# MCont_V1_0.net
KiCad netlist of a schematic drawn in Altium Designer
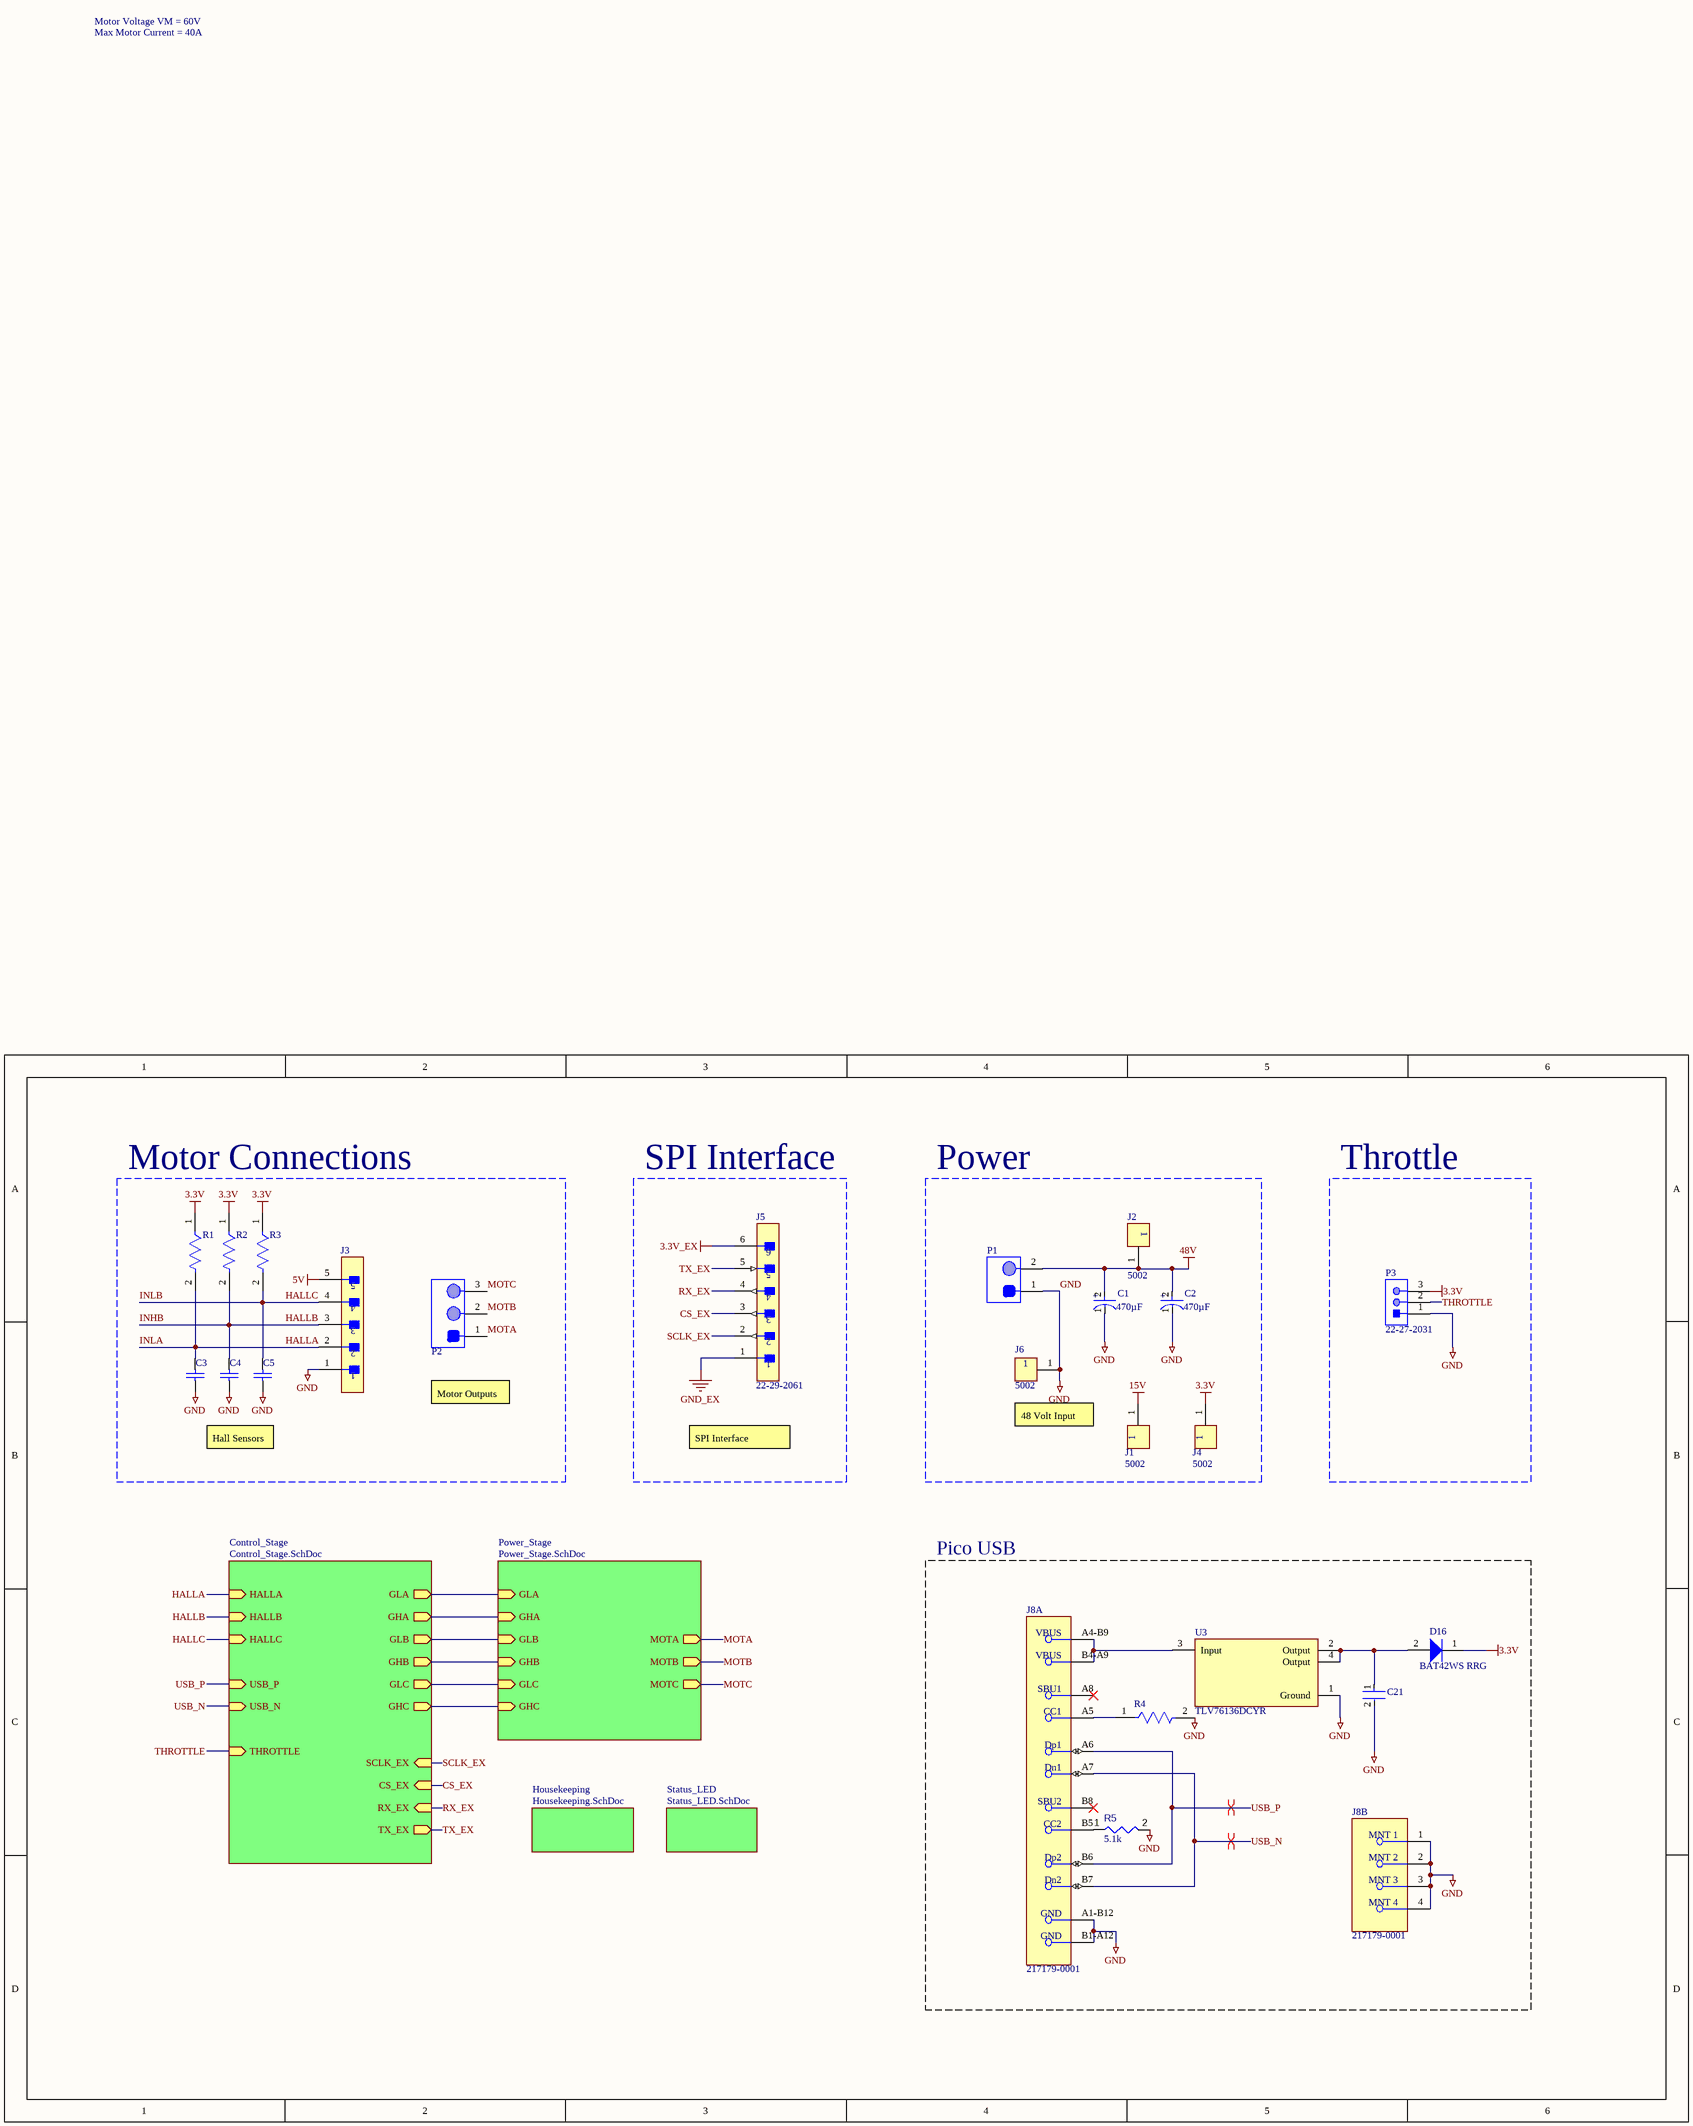
[diagram p0: MCont_V1.0.SchDoc]

(export (version "E")
  (design (tool "Eeschema 10.0.6"))
  (components
    (comp (ref "C1")
      (value "ESH477M100AM2AA")
      (footprint "FP-ESH477M100AM2AA-MFG")
      (description "ESH477M100AM2AA Radial Can ALUMINUM ELECTROLYTIC CAPACITOR ESH 100V 470muF ±20% 0.630Dia 16.00mm")
      (fields (field (name "TOLERANCE") "20%") (field (name "CAPACITANCE") "470µF"))
      (libsource (lib "Altium Content Vault") (part "cf48714ba7e38822c1575c7ec0b6d1f"))
    )
    (comp (ref "C2")
      (value "ESH477M100AM2AA")
      (footprint "FP-ESH477M100AM2AA-MFG")
      (description "ESH477M100AM2AA Radial Can ALUMINUM ELECTROLYTIC CAPACITOR ESH 100V 470muF ±20% 0.630Dia 16.00mm")
      (fields (field (name "TOLERANCE") "20%") (field (name "CAPACITANCE") "470µF"))
      (libsource (lib "Altium Content Vault") (part "cf48714ba7e38822c1575c7ec0b6d1f"))
    )
    (comp (ref "C3")
      (value "VJ0603Y102KXACW1BC")
      (footprint "CAPC1608X95X40NL15T15")
      (fields (field (name "MANUFACTURER") "Vitramon"))
      (libsource (lib "Altium Content Vault") (part "CAP"))
    )
    (comp (ref "C4")
      (value "VJ0603Y102KXACW1BC")
      (footprint "CAPC1608X95X40NL15T15")
      (fields (field (name "MANUFACTURER") "Vitramon"))
      (libsource (lib "Altium Content Vault") (part "CAP"))
    )
    (comp (ref "C5")
      (value "VJ0603Y102KXACW1BC")
      (footprint "CAPC1608X95X40NL15T15")
      (fields (field (name "MANUFACTURER") "Vitramon"))
      (libsource (lib "Altium Content Vault") (part "CAP"))
    )
    (comp (ref "C21")
      (value "CC0603KRX5R6BB106")
      (footprint "FP-CC0603-DC-MFG")
      (description "CAP CER 10UF 10V X5R 0603")
      (fields (field (name "TOLERANCE") "10%"))
      (libsource (lib "Altium Content Vault") (part "b4654b650e69147ec39a6b967a45e02"))
    )
    (comp (ref "D16")
      (value "BAT42WS RRG")
      (footprint "BAT42WS RRG-Footprint-1")
      (description "Schottky Diode, 30V, 0.2A, Sod-323F Rohs Compliant: Yes")
      (libsource (lib "CEV Electrical New") (part "BAT42WS RRG-Symbol-1"))
    )
    (comp (ref "J1")
      (value "5002")
      (footprint "FP-5002-MFG")
      (description "PC TEST POINT MINIATURE WHITE")
      (libsource (lib "") (part "1e4615820a309e3ce90f9e6d957b7fa_1"))
    )
    (comp (ref "J2")
      (value "5002")
      (footprint "FP-5002-MFG")
      (description "PC TEST POINT MINIATURE WHITE")
      (libsource (lib "") (part "1e4615820a309e3ce90f9e6d957b7fa_2"))
    )
    (comp (ref "J3")
      (value "22-29-2051")
      (footprint "FP-22-29-2051-MFG")
      (description "2.54MM KK HDR VT FRICLK VRA .5AU")
      (libsource (lib "Altium Content Vault") (part "bf93c07fd2649a848d0ec8585582aab"))
    )
    (comp (ref "J4")
      (value "5002")
      (footprint "FP-5002-MFG")
      (description "PC TEST POINT MINIATURE WHITE")
      (libsource (lib "") (part "1e4615820a309e3ce90f9e6d957b7fa_1"))
    )
    (comp (ref "J5")
      (value "22-29-2061")
      (footprint "FP-22-29-2061-MFG")
      (description "CONN HEADER VERT 6POS 2.54MM")
      (libsource (lib "Altium Content Vault") (part "f2cb566baf1c37ab5a3b8e90bbeafd6"))
    )
    (comp (ref "J6")
      (value "5002")
      (footprint "FP-5002-MFG")
      (description "PC TEST POINT MINIATURE WHITE")
      (libsource (lib "Altium Content Vault") (part "1e4615820a309e3ce90f9e6d957b7fa"))
    )
    (comp (ref "J8")
      (value "217179-0001")
      (footprint "FP-2171790001-MFG")
      (description "CONN RCP USB2.0 TYP C 24P SMD RA")
      (libsource (lib "Altium Content Vault") (part "8b86497a633d14b3f74642136fc0ce6"))
    )
    (comp (ref "P1")
      (value "VP0265540000G")
      (footprint "VP0265540000G-Footprint-1")
      (description "VP10.16-2P slot screws Cr3+ zinc, solder foot bright tin, steel stamping clamp")
      (libsource (lib "CEV Electrical") (part "VP0265540000G-Symbol-1"))
    )
    (comp (ref "P2")
      (value "VP0365540000G")
      (footprint "VP0365540000G-Footprint-1")
      (description "VP10.16-3P slot screws Cr3 zinc, solder foot bright tin, steel stamping clamp")
      (libsource (lib "CEV Electrical") (part "VP0365540000G-Symbol-1"))
    )
    (comp (ref "P3")
      (value "22-27-2031")
      (footprint "MOLX-22-27-2031_V")
      (fields (field (name "MANUFACTURER") "Molex"))
      (libsource (lib "Altium Content Vault") (part "CN-1P-M-R3"))
    )
    (comp (ref "R1")
      (value "RC0603FR-0710KL")
      (footprint "FP-RC0603-0_55-IPC_C")
      (description "RES 10K OHM 1% 1/10W 0603")
      (fields (field (name "TOLERANCE") "1%"))
      (libsource (lib "Altium Content Vault") (part "1029c3af85768c4190bb7ad29bc67b5"))
    )
    (comp (ref "R2")
      (value "RC0603FR-0710KL")
      (footprint "FP-RC0603-0_55-IPC_C")
      (description "RES 10K OHM 1% 1/10W 0603")
      (fields (field (name "TOLERANCE") "1%"))
      (libsource (lib "Altium Content Vault") (part "1029c3af85768c4190bb7ad29bc67b5"))
    )
    (comp (ref "R3")
      (value "RC0603FR-0710KL")
      (footprint "FP-RC0603-0_55-IPC_C")
      (description "RES 10K OHM 1% 1/10W 0603")
      (fields (field (name "TOLERANCE") "1%"))
      (libsource (lib "Altium Content Vault") (part "1029c3af85768c4190bb7ad29bc67b5"))
    )
    (comp (ref "R4")
      (value "ERJ-3EKF5101V")
      (footprint "FP-ERJ3EK-MFG")
      (description "RES SMD 5.1K OHM 1% 1/10W 0603")
      (fields (field (name "TOLERANCE") "1%"))
      (libsource (lib "Altium Content Vault") (part "1029c3af85768c4190bb7ad29bc67b5"))
    )
    (comp (ref "R5")
      (value "5.1k")
      (footprint "FP-ERJ3EK-IPC_A")
      (fields
        (field (name "TOLERANCE") "1%")
        (field (name "POWER") "100mW")
        (field (name "Comment") "ERJ-3EKF5101V")
      )
      (libsource (lib "CEV Electrical") (part "RES-2"))
    )
    (comp (ref "U3")
      (value "TLV76136DCYR")
      (footprint "TLV76136DCYR-Footprint-1")
      (description "1A 16V high-PSRR linear voltage regulator 4-SOT-223 -40 to 125")
      (libsource (lib "CEV Electrical New") (part "TLV76136DCYR-Symbol-1"))
    )
  )
  (nets
    (net (code "1") (name "/CS_EX") (class "Default")
      (node (ref "J5") (pin "3") (pinfunction "3_3") (pintype "output"))
    )
    (net (code "8") (name "/HALLA") (class "Default")
      (node (ref "C3") (pin "2") (pinfunction "2_2") (pintype "passive"))
      (node (ref "J3") (pin "2") (pinfunction "2_2") (pintype "passive"))
      (node (ref "R1") (pin "2") (pinfunction "2_2") (pintype "passive"))
    )
    (net (code "9") (name "/HALLB") (class "Default")
      (node (ref "C4") (pin "2") (pinfunction "2_2") (pintype "passive"))
      (node (ref "J3") (pin "3") (pinfunction "3_3") (pintype "passive"))
      (node (ref "R2") (pin "2") (pinfunction "2_2") (pintype "passive"))
    )
    (net (code "10") (name "/HALLC") (class "Default")
      (node (ref "C5") (pin "2") (pinfunction "2_2") (pintype "passive"))
      (node (ref "J3") (pin "4") (pinfunction "4_4") (pintype "passive"))
      (node (ref "R3") (pin "2") (pinfunction "2_2") (pintype "passive"))
    )
    (net (code "11") (name "/MOTA") (class "Default")
      (node (ref "P2") (pin "1") (pinfunction "1_1") (pintype "passive"))
    )
    (net (code "12") (name "/MOTB") (class "Default")
      (node (ref "P2") (pin "2") (pinfunction "2_2") (pintype "passive"))
    )
    (net (code "13") (name "/MOTC") (class "Default")
      (node (ref "P2") (pin "3") (pinfunction "3_3") (pintype "passive"))
    )
    (net (code "14") (name "/RX_EX") (class "Default")
      (node (ref "J5") (pin "4") (pinfunction "4_4") (pintype "output"))
    )
    (net (code "15") (name "/SCLK_EX") (class "Default")
      (node (ref "J5") (pin "2") (pinfunction "2_2") (pintype "output"))
    )
    (net (code "16") (name "/THROTTLE") (class "Default")
      (node (ref "P3") (pin "2") (pinfunction "2_2") (pintype "passive"))
    )
    (net (code "17") (name "/TX_EX") (class "Default")
      (node (ref "J5") (pin "5") (pinfunction "5_5") (pintype "input"))
    )
    (net (code "18") (name "/USB_N") (class "Default")
      (node (ref "J8") (pin "A7") (pinfunction "Dn1_A7") (pintype "bidirectional"))
      (node (ref "J8") (pin "B7") (pinfunction "Dn2_B7") (pintype "bidirectional"))
    )
    (net (code "19") (name "/USB_P") (class "Default")
      (node (ref "J8") (pin "A6") (pinfunction "Dp1_A6") (pintype "bidirectional"))
      (node (ref "J8") (pin "B6") (pinfunction "Dp2_B6") (pintype "bidirectional"))
    )
    (net (code "20") (name "3.3V") (class "Default")
      (node (ref "D16") (pin "1") (pinfunction "K_1") (pintype "passive"))
      (node (ref "J4") (pin "1") (pinfunction "1_1") (pintype "passive"))
      (node (ref "P3") (pin "3") (pinfunction "3_3") (pintype "passive"))
      (node (ref "R1") (pin "1") (pinfunction "1_1") (pintype "passive"))
      (node (ref "R2") (pin "1") (pinfunction "1_1") (pintype "passive"))
      (node (ref "R3") (pin "1") (pinfunction "1_1") (pintype "passive"))
    )
    (net (code "21") (name "3.3V_EX") (class "Default")
      (node (ref "J5") (pin "6") (pinfunction "6_6") (pintype "power_in"))
    )
    (net (code "22") (name "5V") (class "Default")
      (node (ref "J3") (pin "5") (pinfunction "5_5") (pintype "passive"))
    )
    (net (code "23") (name "15V") (class "Default")
      (node (ref "J1") (pin "1") (pinfunction "1_1") (pintype "passive"))
    )
    (net (code "24") (name "48V") (class "Default")
      (node (ref "C1") (pin "2") (pinfunction "A_2") (pintype "passive"))
      (node (ref "C2") (pin "2") (pinfunction "A_2") (pintype "passive"))
      (node (ref "J2") (pin "1") (pinfunction "1_1") (pintype "passive"))
      (node (ref "P1") (pin "2") (pinfunction "2_2") (pintype "passive"))
    )
    (net (code "25") (name "GND") (class "Default")
      (node (ref "C1") (pin "1") (pinfunction "C_1") (pintype "passive"))
      (node (ref "C2") (pin "1") (pinfunction "C_1") (pintype "passive"))
      (node (ref "C21") (pin "2") (pinfunction "2_2") (pintype "passive"))
      (node (ref "C3") (pin "1") (pinfunction "1_1") (pintype "passive"))
      (node (ref "C4") (pin "1") (pinfunction "1_1") (pintype "passive"))
      (node (ref "C5") (pin "1") (pinfunction "1_1") (pintype "passive"))
      (node (ref "J3") (pin "1") (pinfunction "1_1") (pintype "passive"))
      (node (ref "J6") (pin "1") (pinfunction "1_1") (pintype "passive"))
      (node (ref "J8") (pin "1") (pinfunction "MNT_1_1") (pintype "passive"))
      (node (ref "J8") (pin "2") (pinfunction "MNT_2_2") (pintype "passive"))
      (node (ref "J8") (pin "3") (pinfunction "MNT_3_3") (pintype "power_in"))
      (node (ref "J8") (pin "4") (pinfunction "MNT_4_4") (pintype "power_in"))
      (node (ref "J8") (pin "A1-B12") (pinfunction "GND_A1-B12") (pintype "power_in"))
      (node (ref "J8") (pin "B1-A12") (pinfunction "GND_B1-A12") (pintype "power_in"))
      (node (ref "P1") (pin "1") (pinfunction "1_1") (pintype "passive"))
      (node (ref "P3") (pin "1") (pinfunction "1_1") (pintype "passive"))
      (node (ref "R4") (pin "2") (pinfunction "2_2") (pintype "passive"))
      (node (ref "R5") (pin "2") (pinfunction "2_2") (pintype "passive"))
      (node (ref "U3") (pin "1") (pinfunction "Ground_1") (pintype "power_in"))
    )
    (net (code "26") (name "GND_EX") (class "Default")
      (node (ref "J5") (pin "1") (pinfunction "1_1") (pintype "power_in"))
    )
    (net (code "27") (name "Net-(D16-A)") (class "Default")
      (node (ref "C21") (pin "1") (pinfunction "1_1") (pintype "passive"))
      (node (ref "D16") (pin "2") (pinfunction "A_2") (pintype "passive"))
      (node (ref "U3") (pin "2") (pinfunction "Output_2") (pintype "passive"))
      (node (ref "U3") (pin "4") (pinfunction "Output_4") (pintype "passive"))
    )
    (net (code "28") (name "Net-(J8A-CC1)") (class "Default")
      (node (ref "J8") (pin "A5") (pinfunction "CC1_A5") (pintype "passive"))
      (node (ref "R4") (pin "1") (pinfunction "1_1") (pintype "passive"))
    )
    (net (code "29") (name "Net-(J8A-CC2)") (class "Default")
      (node (ref "J8") (pin "B5") (pinfunction "CC2_B5") (pintype "passive"))
      (node (ref "R5") (pin "1") (pinfunction "1_1") (pintype "passive"))
    )
    (net (code "30") (name "Net-(U3-Input)") (class "Default")
      (node (ref "J8") (pin "A4-B9") (pinfunction "VBUS_A4-B9") (pintype "power_in"))
      (node (ref "J8") (pin "B4-A9") (pinfunction "VBUS_B4-A9") (pintype "power_in"))
      (node (ref "U3") (pin "3") (pinfunction "Input_3") (pintype "passive"))
    )
    (net (code "31") (name "unconnected-(J8A-SBU1-PadA8)") (class "Default")
      (node (ref "J8") (pin "A8") (pinfunction "SBU1_A8") (pintype "passive+no_connect"))
    )
    (net (code "32") (name "unconnected-(J8A-SBU2-PadB8)") (class "Default")
      (node (ref "J8") (pin "B8") (pinfunction "SBU2_B8") (pintype "passive+no_connect"))
    )
  )
)
